# 6_ESP12_F.net
KiCad netlist of a schematic drawn in Altium Designer
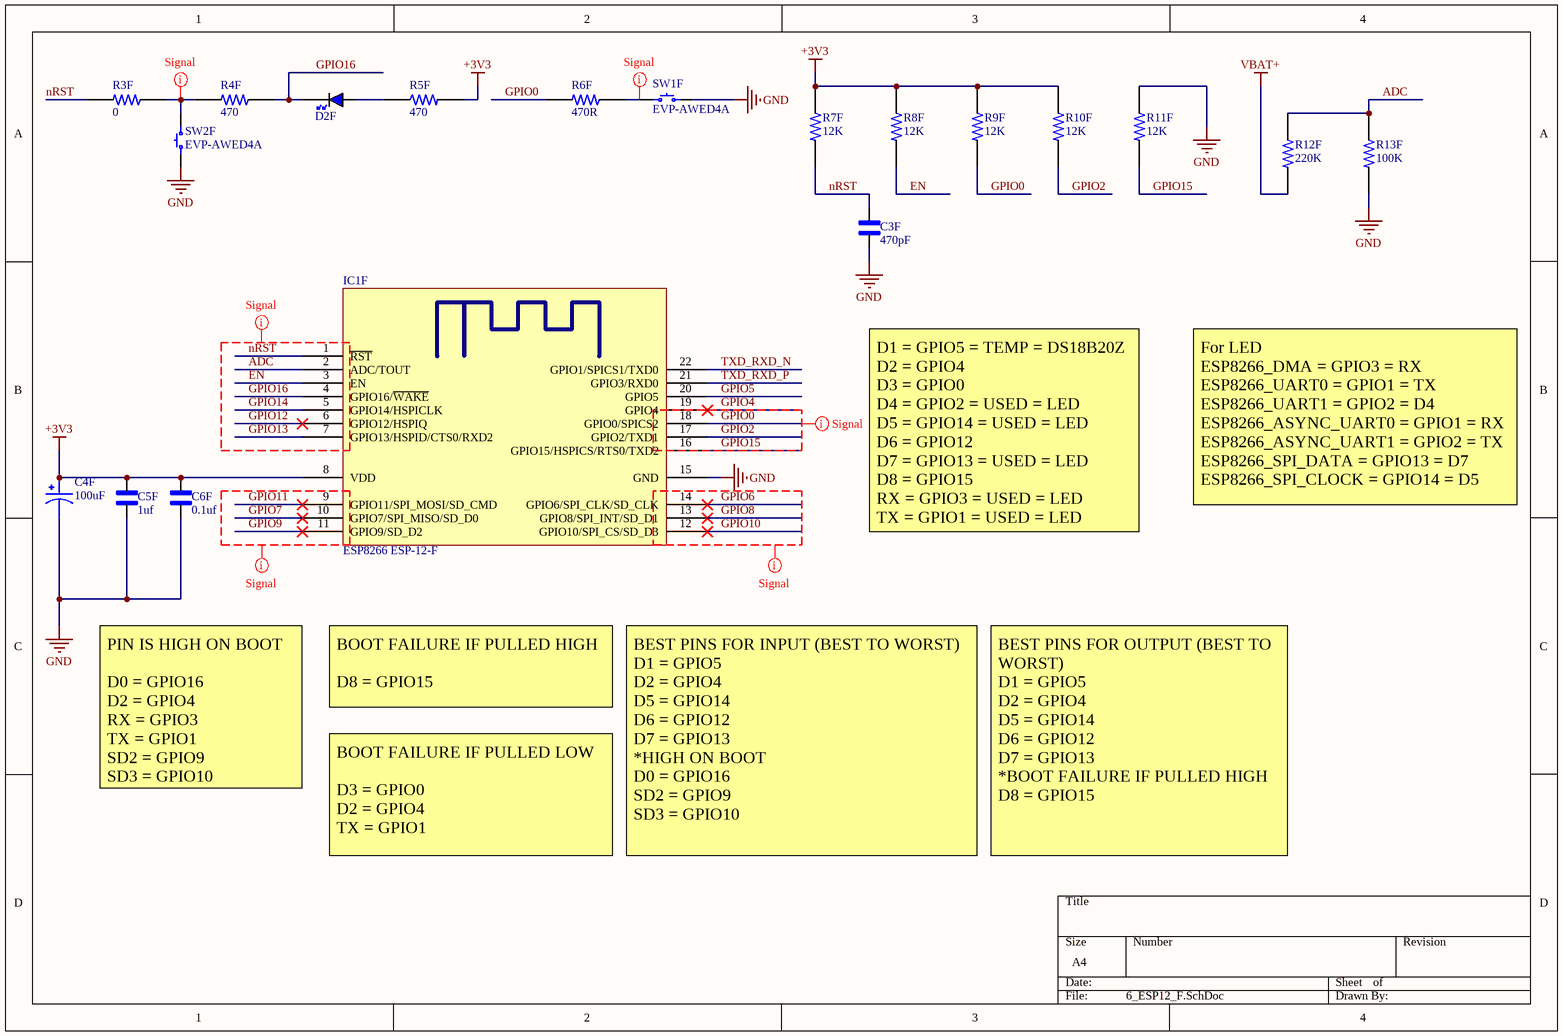
[diagram p0: 6_ESP12_F.SchDoc]

(export (version "E")
  (design (tool "Eeschema 10.0.6"))
  (components
    (comp (ref "C3F")
      (value "470pF")
      (footprint "C-0603")
      (description "Ceramic Capacitor 16V 0603 (1608 Metric)")
      (fields (field (name "MP") "C0603C104J4RAC") (field (name "MF") "KEMET"))
      (libsource (lib "ESP-12F_WLED_IOT_LIPO") (part "C-0603"))
    )
    (comp (ref "C4F")
      (value "100uF")
      (footprint "1411-3528")
      (description "Molded Tantalum Capacitors 16V 1411 (3528 Metric)")
      (fields (field (name "MF") "KEMET") (field (name "MP") "T495B106K025ATE750"))
      (libsource (lib "ESP-12F_WLED_IOT_LIPO") (part "C-1411 (3528 Metric)"))
    )
    (comp (ref "C5F")
      (value "1uf")
      (footprint "C-0603")
      (description "Ceramic Capacitor 16V 0603 (1608 Metric)")
      (fields (field (name "MP") "C0603C104J4RAC") (field (name "MF") "KEMET"))
      (libsource (lib "ESP-12F_WLED_IOT_LIPO") (part "C-0603"))
    )
    (comp (ref "C6F")
      (value "0.1uf")
      (footprint "C-0603")
      (description "Ceramic Capacitor 16V 0603 (1608 Metric)")
      (fields (field (name "MP") "C0603C104J4RAC") (field (name "MF") "KEMET"))
      (libsource (lib "ESP-12F_WLED_IOT_LIPO") (part "C-0603"))
    )
    (comp (ref "D2F")
      (value "BLUE")
      (footprint "LED_0603_BLUE")
      (description "LED 0603 BLUE SMD")
      (libsource (lib "ESP-12F_WLED_IOT_LIPO") (part "LED_0603_BLUE"))
    )
    (comp (ref "IC1F")
      (value "ESP8266 ESP-12-F")
      (footprint "ESP8266:ESP8266 ESP-12-F")
      (libsource (lib "ESP-12F_WLED_IOT_LIPO") (part "ESP8266 ESP-12-F"))
    )
    (comp (ref "R3F")
      (value "0")
      (footprint "R-0603")
      (description "0603")
      (fields (field (name "MP") "2-1623703-0") (field (name "TOLERANCE") "1%"))
      (libsource (lib "ESP-12F_WLED_IOT_LIPO") (part "R-0603"))
    )
    (comp (ref "R4F")
      (value "470")
      (footprint "R-0603")
      (description "0603")
      (fields (field (name "MP") "2-1623703-0") (field (name "TOLERANCE") "1%"))
      (libsource (lib "ESP-12F_WLED_IOT_LIPO") (part "R-0603"))
    )
    (comp (ref "R5F")
      (value "470")
      (footprint "R-0603")
      (description "0603")
      (fields (field (name "MP") "2-1623703-0") (field (name "TOLERANCE") "1%"))
      (libsource (lib "ESP-12F_WLED_IOT_LIPO") (part "R-0603"))
    )
    (comp (ref "R6F")
      (value "470R")
      (footprint "R-0603")
      (description "0603")
      (fields (field (name "MP") "2-1623703-0") (field (name "TOLERANCE") "1%"))
      (libsource (lib "ESP-12F_WLED_IOT_LIPO") (part "R-0603"))
    )
    (comp (ref "R7F")
      (value "12K")
      (footprint "R-0603")
      (description "0603")
      (fields (field (name "MP") "2-1623703-0") (field (name "TOLERANCE") "1%"))
      (libsource (lib "ESP-12F_WLED_IOT_LIPO") (part "R-0603"))
    )
    (comp (ref "R8F")
      (value "12K")
      (footprint "R-0603")
      (description "0603")
      (fields (field (name "MP") "2-1623703-0") (field (name "TOLERANCE") "1%"))
      (libsource (lib "ESP-12F_WLED_IOT_LIPO") (part "R-0603"))
    )
    (comp (ref "R9F")
      (value "12K")
      (footprint "R-0603")
      (description "0603")
      (fields (field (name "MP") "2-1623703-0") (field (name "TOLERANCE") "1%"))
      (libsource (lib "ESP-12F_WLED_IOT_LIPO") (part "R-0603"))
    )
    (comp (ref "R10F")
      (value "12K")
      (footprint "R-0603")
      (description "0603")
      (fields (field (name "MP") "2-1623703-0") (field (name "TOLERANCE") "1%"))
      (libsource (lib "ESP-12F_WLED_IOT_LIPO") (part "R-0603"))
    )
    (comp (ref "R11F")
      (value "12K")
      (footprint "R-0603")
      (description "0603")
      (fields (field (name "MP") "2-1623703-0") (field (name "TOLERANCE") "1%"))
      (libsource (lib "ESP-12F_WLED_IOT_LIPO") (part "R-0603"))
    )
    (comp (ref "R12F")
      (value "220K")
      (footprint "R-0603")
      (description "0603")
      (fields (field (name "MP") "2-1623703-0") (field (name "TOLERANCE") "1%"))
      (libsource (lib "ESP-12F_WLED_IOT_LIPO") (part "R-0603"))
    )
    (comp (ref "R13F")
      (value "100K")
      (footprint "R-0603")
      (description "0603")
      (fields (field (name "MP") "2-1623703-0") (field (name "TOLERANCE") "1%"))
      (libsource (lib "ESP-12F_WLED_IOT_LIPO") (part "R-0603"))
    )
    (comp (ref "SW1F")
      (value "EVP-AWED4A")
      (footprint "PANASONIC EVPAW")
      (description "3.0MM X 2.0MM / 3.3N / 0.15MM ST")
      (fields (field (name "MANUFACTURER") "Panasonic Electronic Components"))
      (libsource (lib "ESP-12F_WLED_IOT_LIPO") (part "SPST-NO 2 PIN"))
    )
    (comp (ref "SW2F")
      (value "EVP-AWED4A")
      (footprint "PANASONIC EVPAW")
      (description "3.0MM X 2.0MM / 3.3N / 0.15MM ST")
      (fields (field (name "MANUFACTURER") "Panasonic Electronic Components"))
      (libsource (lib "ESP-12F_WLED_IOT_LIPO") (part "SPST-NO 2 PIN"))
    )
  )
  (nets
    (net (code "1") (name "+3V3") (class "Default")
      (node (ref "C4F") (pin "1") (pinfunction "1_1") (pintype "passive"))
      (node (ref "C5F") (pin "2") (pinfunction "2_2") (pintype "passive"))
      (node (ref "C6F") (pin "2") (pinfunction "2_2") (pintype "passive"))
      (node (ref "IC1F") (pin "8") (pinfunction "VDD_8") (pintype "passive"))
      (node (ref "R10F") (pin "1") (pinfunction "1_1") (pintype "passive"))
      (node (ref "R5F") (pin "2") (pinfunction "2_2") (pintype "passive"))
      (node (ref "R7F") (pin "1") (pinfunction "1_1") (pintype "passive"))
      (node (ref "R8F") (pin "1") (pinfunction "1_1") (pintype "passive"))
      (node (ref "R9F") (pin "1") (pinfunction "1_1") (pintype "passive"))
    )
    (net (code "2") (name "/ADC") (class "Default")
      (node (ref "IC1F") (pin "2") (pinfunction "ADC/TOUT_2") (pintype "passive"))
      (node (ref "R12F") (pin "1") (pinfunction "1_1") (pintype "passive"))
      (node (ref "R13F") (pin "1") (pinfunction "1_1") (pintype "passive"))
    )
    (net (code "3") (name "/EN") (class "Default")
      (node (ref "IC1F") (pin "3") (pinfunction "EN_3") (pintype "passive"))
      (node (ref "R8F") (pin "2") (pinfunction "2_2") (pintype "passive"))
    )
    (net (code "4") (name "/GPIO0") (class "Default")
      (node (ref "IC1F") (pin "18") (pinfunction "GPIO0/SPICS2_18") (pintype "passive"))
      (node (ref "R6F") (pin "2") (pinfunction "2_2") (pintype "passive"))
      (node (ref "R9F") (pin "2") (pinfunction "2_2") (pintype "passive"))
    )
    (net (code "5") (name "/GPIO2") (class "Default")
      (node (ref "IC1F") (pin "17") (pinfunction "GPIO2/TXD1_17") (pintype "passive"))
      (node (ref "R10F") (pin "2") (pinfunction "2_2") (pintype "passive"))
    )
    (net (code "6") (name "/GPIO4") (class "Default")
      (node (ref "IC1F") (pin "19") (pinfunction "GPIO4_19") (pintype "passive+no_connect"))
    )
    (net (code "7") (name "/GPIO5") (class "Default")
      (node (ref "IC1F") (pin "20") (pinfunction "GPIO5_20") (pintype "passive"))
    )
    (net (code "8") (name "/GPIO6") (class "Default")
      (node (ref "IC1F") (pin "14") (pinfunction "GPIO6/SPI_CLK/SD_CLK_14") (pintype "passive+no_connect"))
    )
    (net (code "9") (name "/GPIO7") (class "Default")
      (node (ref "IC1F") (pin "10") (pinfunction "GPIO7/SPI_MISO/SD_D0_10") (pintype "passive+no_connect"))
    )
    (net (code "10") (name "/GPIO8") (class "Default")
      (node (ref "IC1F") (pin "13") (pinfunction "GPIO8/SPI_INT/SD_D1_13") (pintype "passive+no_connect"))
    )
    (net (code "11") (name "/GPIO9") (class "Default")
      (node (ref "IC1F") (pin "11") (pinfunction "GPIO9/SD_D2_11") (pintype "passive+no_connect"))
    )
    (net (code "12") (name "/GPIO10") (class "Default")
      (node (ref "IC1F") (pin "12") (pinfunction "GPIO10/SPI_CS/SD_D3_12") (pintype "passive+no_connect"))
    )
    (net (code "13") (name "/GPIO11") (class "Default")
      (node (ref "IC1F") (pin "9") (pinfunction "GPIO11/SPI_MOSI/SD_CMD_9") (pintype "passive+no_connect"))
    )
    (net (code "14") (name "/GPIO12") (class "Default")
      (node (ref "IC1F") (pin "6") (pinfunction "GPIO12/HSPIQ_6") (pintype "passive+no_connect"))
    )
    (net (code "15") (name "/GPIO13") (class "Default")
      (node (ref "IC1F") (pin "7") (pinfunction "GPIO13/HSPID/CTS0/RXD2_7") (pintype "passive"))
    )
    (net (code "16") (name "/GPIO14") (class "Default")
      (node (ref "IC1F") (pin "5") (pinfunction "GPIO14/HSPICLK_5") (pintype "passive"))
    )
    (net (code "17") (name "/GPIO15") (class "Default")
      (node (ref "IC1F") (pin "16") (pinfunction "GPIO15/HSPICS/RTS0/TXD2_16") (pintype "passive"))
      (node (ref "R11F") (pin "2") (pinfunction "2_2") (pintype "passive"))
    )
    (net (code "18") (name "/GPIO16") (class "Default")
      (node (ref "D2F") (pin "K") (pinfunction "K_K") (pintype "passive"))
      (node (ref "IC1F") (pin "4") (pinfunction "GPIO16/~{WAKE}_4") (pintype "passive"))
      (node (ref "R4F") (pin "1") (pinfunction "1_1") (pintype "passive"))
    )
    (net (code "19") (name "/TXD_RXD_N") (class "Default")
      (node (ref "IC1F") (pin "22") (pinfunction "GPIO1/SPICS1/TXD0_22") (pintype "passive"))
    )
    (net (code "20") (name "/TXD_RXD_P") (class "Default")
      (node (ref "IC1F") (pin "21") (pinfunction "GPIO3/RXD0_21") (pintype "passive"))
    )
    (net (code "21") (name "/nRST") (class "Default")
      (node (ref "C3F") (pin "2") (pinfunction "2_2") (pintype "passive"))
      (node (ref "IC1F") (pin "1") (pinfunction "~{RST}_1") (pintype "passive"))
      (node (ref "R3F") (pin "2") (pinfunction "2_2") (pintype "passive"))
      (node (ref "R7F") (pin "2") (pinfunction "2_2") (pintype "passive"))
    )
    (net (code "22") (name "GND") (class "Default")
      (node (ref "C3F") (pin "1") (pinfunction "1_1") (pintype "passive"))
      (node (ref "C4F") (pin "2") (pinfunction "2_2") (pintype "passive"))
      (node (ref "C5F") (pin "1") (pinfunction "1_1") (pintype "passive"))
      (node (ref "C6F") (pin "1") (pinfunction "1_1") (pintype "passive"))
      (node (ref "IC1F") (pin "15") (pinfunction "GND_15") (pintype "passive"))
      (node (ref "R11F") (pin "1") (pinfunction "1_1") (pintype "passive"))
      (node (ref "R13F") (pin "2") (pinfunction "2_2") (pintype "passive"))
      (node (ref "SW1F") (pin "2") (pinfunction "2_2") (pintype "passive"))
      (node (ref "SW2F") (pin "1") (pinfunction "1_1") (pintype "passive"))
    )
    (net (code "23") (name "Net-(D2F-PadA)") (class "Default")
      (node (ref "D2F") (pin "A") (pinfunction "A_A") (pintype "passive"))
      (node (ref "R5F") (pin "1") (pinfunction "1_1") (pintype "passive"))
    )
    (net (code "24") (name "Net-(R3F-Pad1)") (class "Default")
      (node (ref "R3F") (pin "1") (pinfunction "1_1") (pintype "passive"))
      (node (ref "R4F") (pin "2") (pinfunction "2_2") (pintype "passive"))
      (node (ref "SW2F") (pin "2") (pinfunction "2_2") (pintype "passive"))
    )
    (net (code "25") (name "Net-(R6F-Pad1)") (class "Default")
      (node (ref "R6F") (pin "1") (pinfunction "1_1") (pintype "passive"))
      (node (ref "SW1F") (pin "1") (pinfunction "1_1") (pintype "passive"))
    )
    (net (code "26") (name "VBAT+") (class "Default")
      (node (ref "R12F") (pin "2") (pinfunction "2_2") (pintype "passive"))
    )
  )
)
